# Payload_Electronics.net
KiCad netlist of a schematic drawn in EAGLE
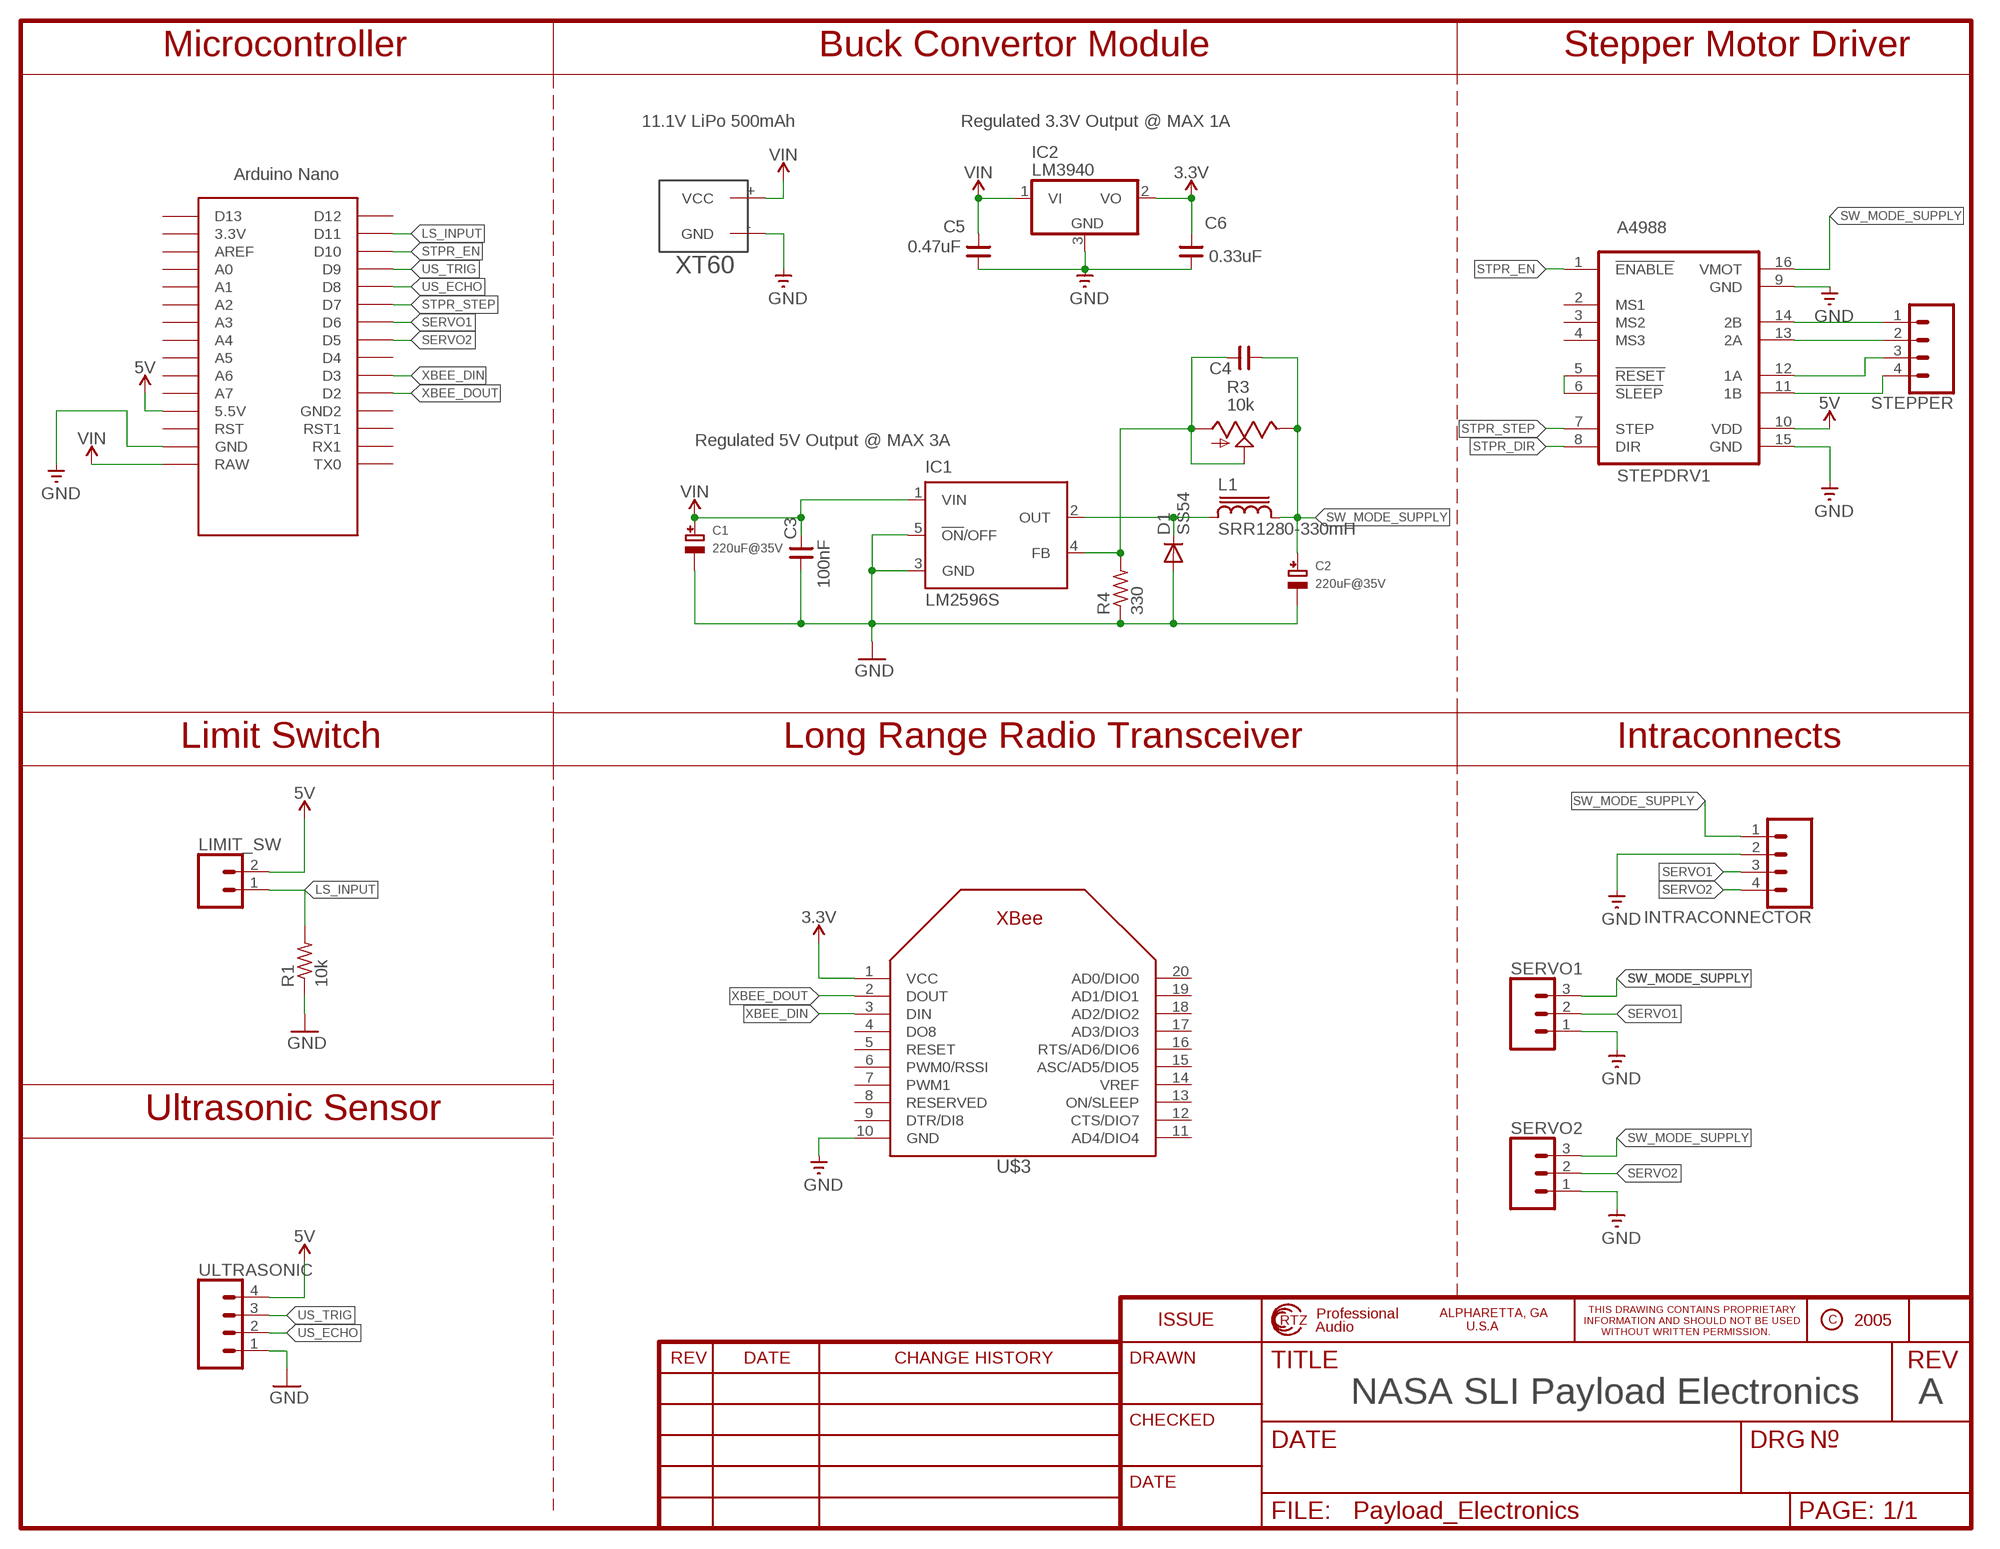
[diagram p0: schematic, sheet 1]

(export (version "E")
  (design (tool "Eeschema 10.0.6"))
  (components
    (comp (ref "C1")
      (value "220uF@35V")
      (footprint "eagle-import:PANASONIC_D")
      (libsource (lib "eagle-import") (part "CAP_ELECTROLYTICPANASONIC_D"))
    )
    (comp (ref "C2")
      (value "220uF@35V")
      (footprint "eagle-import:PANASONIC_D")
      (libsource (lib "eagle-import") (part "CAP_ELECTROLYTICPANASONIC_D"))
    )
    (comp (ref "C3")
      (value "100nF")
      (footprint "eagle-import:0603")
      (libsource (lib "eagle-import") (part "CNP-0603"))
    )
    (comp (ref "C4")
      (value "CNP-0603")
      (footprint "eagle-import:0603")
      (libsource (lib "eagle-import") (part "CNP-0603"))
    )
    (comp (ref "C5")
      (value "0.47uF")
      (footprint "eagle-import:0805")
      (libsource (lib "eagle-import") (part "CNP-0805"))
    )
    (comp (ref "C6")
      (value "0.33uF")
      (footprint "eagle-import:0805")
      (libsource (lib "eagle-import") (part "CNP-0805"))
    )
    (comp (ref "D1")
      (value "SS54")
      (footprint "eagle-import:DO214AB")
      (fields (field (name "MF") "Fairchild") (field (name "MPN") "S3G"))
      (libsource (lib "eagle-import") (part "S3G"))
    )
    (comp (ref "IC1")
      (value "LM2596S")
      (footprint "eagle-import:TO263-5")
      (fields (field (name "MF") "NATIONAL SEMICONDUCTOR") (field (name "MPN") "LM2596S-ADJ/NOPB"))
      (libsource (lib "eagle-import") (part "LM2596S"))
    )
    (comp (ref "IC2")
      (value "LM3940")
      (footprint "eagle-import:TO252")
      (libsource (lib "eagle-import") (part "78DT15"))
    )
    (comp (ref "INTRACONNECTOR")
      (value "CONN_04")
      (footprint "eagle-import:1X04")
      (libsource (lib "eagle-import") (part "CONN_04"))
    )
    (comp (ref "L1")
      (value "SRR1280-330mH")
      (footprint "eagle-import:SRR1280")
      (libsource (lib "eagle-import") (part "SRR1280"))
    )
    (comp (ref "LIMIT_SW")
      (value "CONN_02")
      (footprint "eagle-import:1X02")
      (libsource (lib "eagle-import") (part "CONN_02"))
    )
    (comp (ref "R1")
      (value "10k")
      (footprint "eagle-import:M0805")
      (libsource (lib "eagle-import") (part "R-US_M0805"))
    )
    (comp (ref "R3")
      (value "10k")
      (footprint "eagle-import:S64W")
      (libsource (lib "eagle-import") (part "TRIM_US-S64W"))
    )
    (comp (ref "R4")
      (value "330")
      (footprint "eagle-import:R0603")
      (libsource (lib "eagle-import") (part "R-US_R0603"))
    )
    (comp (ref "SERVO1")
      (value "CONN_03")
      (footprint "eagle-import:1X03")
      (libsource (lib "eagle-import") (part "CONN_03"))
    )
    (comp (ref "SERVO2")
      (value "CONN_03")
      (footprint "eagle-import:1X03")
      (libsource (lib "eagle-import") (part "CONN_03"))
    )
    (comp (ref "STEPDRV1")
      (value "A4988")
      (footprint "eagle-import:POLOLULU2128")
      (libsource (lib "eagle-import") (part "POLOLULU2128"))
    )
    (comp (ref "STEPPER")
      (value "CONN_04")
      (footprint "eagle-import:1X04")
      (libsource (lib "eagle-import") (part "CONN_04"))
    )
    (comp (ref "U$1")
      (value "NANO")
      (footprint "eagle-import:NANO")
      (libsource (lib "eagle-import") (part "NANO"))
    )
    (comp (ref "U$2")
      (value "XT60")
      (footprint "eagle-import:XT60")
      (libsource (lib "eagle-import") (part "XT60"))
    )
    (comp (ref "U$3")
      (value "XBEE")
      (footprint "eagle-import:XBEE")
      (libsource (lib "eagle-import") (part "XBEE"))
    )
    (comp (ref "ULTRASONIC")
      (value "CONN_04")
      (footprint "eagle-import:1X04")
      (libsource (lib "eagle-import") (part "CONN_04"))
    )
  )
  (nets
    (net (code "1") (name "3.3V") (class "Default")
      (node (ref "C6") (pin "2") (pinfunction "2_2") (pintype "passive"))
      (node (ref "IC2") (pin "2") (pinfunction "VO_2") (pintype "passive"))
      (node (ref "U$3") (pin "1") (pinfunction "VCC_1") (pintype "power_in"))
    )
    (net (code "2") (name "5V") (class "Default")
      (node (ref "LIMIT_SW") (pin "2") (pinfunction "2_2") (pintype "passive"))
      (node (ref "STEPDRV1") (pin "10") (pinfunction "VDD_10") (pintype "power_in"))
      (node (ref "U$1") (pin "5V") (pinfunction "5.5V_5V") (pintype "bidirectional"))
      (node (ref "ULTRASONIC") (pin "4") (pinfunction "4_4") (pintype "passive"))
    )
    (net (code "3") (name "GND") (class "Default")
      (node (ref "C1") (pin "-") (pinfunction "-_-") (pintype "passive"))
      (node (ref "C2") (pin "-") (pinfunction "-_-") (pintype "passive"))
      (node (ref "C3") (pin "1") (pinfunction "1_1") (pintype "passive"))
      (node (ref "C5") (pin "1") (pinfunction "1_1") (pintype "passive"))
      (node (ref "C6") (pin "1") (pinfunction "1_1") (pintype "passive"))
      (node (ref "D1") (pin "A") (pinfunction "A_A") (pintype "passive"))
      (node (ref "IC1") (pin "3") (pinfunction "GND_3") (pintype "power_in"))
      (node (ref "IC1") (pin "5") (pinfunction "~{ON}/OFF_5") (pintype "input"))
      (node (ref "IC2") (pin "3") (pinfunction "GND_3") (pintype "passive"))
      (node (ref "INTRACONNECTOR") (pin "2") (pinfunction "2_2") (pintype "passive"))
      (node (ref "R1") (pin "1") (pinfunction "1_1") (pintype "passive"))
      (node (ref "R4") (pin "1") (pinfunction "1_1") (pintype "passive"))
      (node (ref "SERVO1") (pin "1") (pinfunction "1_1") (pintype "passive"))
      (node (ref "SERVO2") (pin "1") (pinfunction "1_1") (pintype "passive"))
      (node (ref "STEPDRV1") (pin "15") (pinfunction "GND_15") (pintype "power_in"))
      (node (ref "STEPDRV1") (pin "9") (pinfunction "GND_9") (pintype "power_in"))
      (node (ref "U$1") (pin "GND") (pinfunction "GND_GND") (pintype "bidirectional"))
      (node (ref "U$2") (pin "-") (pinfunction "GND_-") (pintype "bidirectional"))
      (node (ref "U$3") (pin "10") (pinfunction "GND_10") (pintype "power_in"))
      (node (ref "ULTRASONIC") (pin "1") (pinfunction "1_1") (pintype "passive"))
    )
    (net (code "4") (name "LS_INPUT") (class "Default")
      (node (ref "LIMIT_SW") (pin "1") (pinfunction "1_1") (pintype "passive"))
      (node (ref "R1") (pin "2") (pinfunction "2_2") (pintype "passive"))
      (node (ref "U$1") (pin "D11") (pinfunction "D11_D11") (pintype "bidirectional"))
    )
    (net (code "5") (name "Net-(IC1-FB)") (class "Default")
      (node (ref "C4") (pin "2") (pinfunction "2_2") (pintype "passive"))
      (node (ref "IC1") (pin "4") (pinfunction "FB_4") (pintype "input"))
      (node (ref "R3") (pin "A") (pinfunction "A_A") (pintype "passive"))
      (node (ref "R3") (pin "S") (pinfunction "S_S") (pintype "passive"))
      (node (ref "R4") (pin "2") (pinfunction "2_2") (pintype "passive"))
    )
    (net (code "6") (name "Net-(IC1-OUT)") (class "Default")
      (node (ref "D1") (pin "C") (pinfunction "C_C") (pintype "passive"))
      (node (ref "IC1") (pin "2") (pinfunction "OUT_2") (pintype "output"))
      (node (ref "L1") (pin "1") (pinfunction "1_1") (pintype "passive"))
    )
    (net (code "7") (name "Net-(STEPDRV1-1A)") (class "Default")
      (node (ref "STEPDRV1") (pin "12") (pinfunction "1A_12") (pintype "output"))
      (node (ref "STEPPER") (pin "3") (pinfunction "3_3") (pintype "passive"))
    )
    (net (code "8") (name "Net-(STEPDRV1-1B)") (class "Default")
      (node (ref "STEPDRV1") (pin "11") (pinfunction "1B_11") (pintype "output"))
      (node (ref "STEPPER") (pin "4") (pinfunction "4_4") (pintype "passive"))
    )
    (net (code "9") (name "Net-(STEPDRV1-2A)") (class "Default")
      (node (ref "STEPDRV1") (pin "13") (pinfunction "2A_13") (pintype "output"))
      (node (ref "STEPPER") (pin "2") (pinfunction "2_2") (pintype "passive"))
    )
    (net (code "10") (name "Net-(STEPDRV1-2B)") (class "Default")
      (node (ref "STEPDRV1") (pin "14") (pinfunction "2B_14") (pintype "output"))
      (node (ref "STEPPER") (pin "1") (pinfunction "1_1") (pintype "passive"))
    )
    (net (code "11") (name "Net-(STEPDRV1-~{RESET})") (class "Default")
      (node (ref "STEPDRV1") (pin "5") (pinfunction "~{RESET}_5") (pintype "input"))
      (node (ref "STEPDRV1") (pin "6") (pinfunction "~{SLEEP}_6") (pintype "input"))
    )
    (net (code "12") (name "SERVO1") (class "Default")
      (node (ref "INTRACONNECTOR") (pin "3") (pinfunction "3_3") (pintype "passive"))
      (node (ref "SERVO1") (pin "2") (pinfunction "2_2") (pintype "passive"))
      (node (ref "U$1") (pin "D6") (pinfunction "D6_D6") (pintype "bidirectional"))
    )
    (net (code "13") (name "SERVO2") (class "Default")
      (node (ref "INTRACONNECTOR") (pin "4") (pinfunction "4_4") (pintype "passive"))
      (node (ref "SERVO2") (pin "2") (pinfunction "2_2") (pintype "passive"))
      (node (ref "U$1") (pin "D5") (pinfunction "D5_D5") (pintype "bidirectional"))
    )
    (net (code "14") (name "STPR_DIR") (class "Default")
      (node (ref "STEPDRV1") (pin "8") (pinfunction "DIR_8") (pintype "input"))
    )
    (net (code "15") (name "STPR_EN") (class "Default")
      (node (ref "STEPDRV1") (pin "1") (pinfunction "~{ENABLE}_1") (pintype "input"))
      (node (ref "U$1") (pin "D10") (pinfunction "D10_D10") (pintype "bidirectional"))
    )
    (net (code "16") (name "STPR_STEP") (class "Default")
      (node (ref "STEPDRV1") (pin "7") (pinfunction "STEP_7") (pintype "input"))
      (node (ref "U$1") (pin "D7") (pinfunction "D7_D7") (pintype "bidirectional"))
    )
    (net (code "17") (name "SW_MODE_SUPPLY") (class "Default")
      (node (ref "C2") (pin "+") (pinfunction "+_+") (pintype "passive"))
      (node (ref "C4") (pin "1") (pinfunction "1_1") (pintype "passive"))
      (node (ref "INTRACONNECTOR") (pin "1") (pinfunction "1_1") (pintype "passive"))
      (node (ref "L1") (pin "2") (pinfunction "2_2") (pintype "passive"))
      (node (ref "R3") (pin "E") (pinfunction "E_E") (pintype "passive"))
      (node (ref "SERVO1") (pin "3") (pinfunction "3_3") (pintype "passive"))
      (node (ref "SERVO2") (pin "3") (pinfunction "3_3") (pintype "passive"))
      (node (ref "STEPDRV1") (pin "16") (pinfunction "VMOT_16") (pintype "power_in"))
    )
    (net (code "18") (name "US_ECHO") (class "Default")
      (node (ref "U$1") (pin "D8") (pinfunction "D8_D8") (pintype "bidirectional"))
      (node (ref "ULTRASONIC") (pin "2") (pinfunction "2_2") (pintype "passive"))
    )
    (net (code "19") (name "US_TRIG") (class "Default")
      (node (ref "U$1") (pin "D9") (pinfunction "D9_D9") (pintype "bidirectional"))
      (node (ref "ULTRASONIC") (pin "3") (pinfunction "3_3") (pintype "passive"))
    )
    (net (code "20") (name "VIN") (class "Default")
      (node (ref "C1") (pin "+") (pinfunction "+_+") (pintype "passive"))
      (node (ref "C3") (pin "2") (pinfunction "2_2") (pintype "passive"))
      (node (ref "C5") (pin "2") (pinfunction "2_2") (pintype "passive"))
      (node (ref "IC1") (pin "1") (pinfunction "VIN_1") (pintype "input"))
      (node (ref "IC2") (pin "1") (pinfunction "VI_1") (pintype "input"))
      (node (ref "U$1") (pin "RAW") (pinfunction "RAW_RAW") (pintype "bidirectional"))
      (node (ref "U$2") (pin "+") (pinfunction "VCC_+") (pintype "bidirectional"))
    )
    (net (code "21") (name "XBEE_DIN") (class "Default")
      (node (ref "U$1") (pin "D3") (pinfunction "D3_D3") (pintype "bidirectional"))
      (node (ref "U$3") (pin "3") (pinfunction "DIN_3") (pintype "input"))
    )
    (net (code "22") (name "XBEE_DOUT") (class "Default")
      (node (ref "U$1") (pin "D2") (pinfunction "D2_D2") (pintype "bidirectional"))
      (node (ref "U$3") (pin "2") (pinfunction "DOUT_2") (pintype "output"))
    )
    (net (code "23") (name "unconnected-(STEPDRV1-MS1-Pad2)") (class "Default")
      (node (ref "STEPDRV1") (pin "2") (pinfunction "MS1_2") (pintype "input"))
    )
    (net (code "24") (name "unconnected-(STEPDRV1-MS2-Pad3)") (class "Default")
      (node (ref "STEPDRV1") (pin "3") (pinfunction "MS2_3") (pintype "input"))
    )
    (net (code "25") (name "unconnected-(STEPDRV1-MS3-Pad4)") (class "Default")
      (node (ref "STEPDRV1") (pin "4") (pinfunction "MS3_4") (pintype "input"))
    )
    (net (code "26") (name "unconnected-(U$1-GND2-PadGND1)") (class "Default")
      (node (ref "U$1") (pin "GND1") (pinfunction "GND2_GND1") (pintype "bidirectional"))
    )
    (net (code "27") (name "unconnected-(U$1-Pad3.3V)") (class "Default")
      (node (ref "U$1") (pin "3.3V") (pinfunction "3.3V_3.3V") (pintype "bidirectional"))
    )
    (net (code "28") (name "unconnected-(U$1-PadA0)") (class "Default")
      (node (ref "U$1") (pin "A0") (pinfunction "A0_A0") (pintype "bidirectional"))
    )
    (net (code "29") (name "unconnected-(U$1-PadA1)") (class "Default")
      (node (ref "U$1") (pin "A1") (pinfunction "A1_A1") (pintype "bidirectional"))
    )
    (net (code "30") (name "unconnected-(U$1-PadA2)") (class "Default")
      (node (ref "U$1") (pin "A2") (pinfunction "A2_A2") (pintype "bidirectional"))
    )
    (net (code "31") (name "unconnected-(U$1-PadA3)") (class "Default")
      (node (ref "U$1") (pin "A3") (pinfunction "A3_A3") (pintype "bidirectional"))
    )
    (net (code "32") (name "unconnected-(U$1-PadA4)") (class "Default")
      (node (ref "U$1") (pin "A4") (pinfunction "A4_A4") (pintype "bidirectional"))
    )
    (net (code "33") (name "unconnected-(U$1-PadA5)") (class "Default")
      (node (ref "U$1") (pin "A5") (pinfunction "A5_A5") (pintype "bidirectional"))
    )
    (net (code "34") (name "unconnected-(U$1-PadA6)") (class "Default")
      (node (ref "U$1") (pin "A6") (pinfunction "A6_A6") (pintype "bidirectional"))
    )
    (net (code "35") (name "unconnected-(U$1-PadA7)") (class "Default")
      (node (ref "U$1") (pin "A7") (pinfunction "A7_A7") (pintype "bidirectional"))
    )
    (net (code "36") (name "unconnected-(U$1-PadAREF)") (class "Default")
      (node (ref "U$1") (pin "AREF") (pinfunction "AREF_AREF") (pintype "bidirectional"))
    )
    (net (code "37") (name "unconnected-(U$1-PadD4)") (class "Default")
      (node (ref "U$1") (pin "D4") (pinfunction "D4_D4") (pintype "bidirectional"))
    )
    (net (code "38") (name "unconnected-(U$1-PadD12)") (class "Default")
      (node (ref "U$1") (pin "D12") (pinfunction "D12_D12") (pintype "bidirectional"))
    )
    (net (code "39") (name "unconnected-(U$1-PadD13)") (class "Default")
      (node (ref "U$1") (pin "D13") (pinfunction "D13_D13") (pintype "bidirectional"))
    )
    (net (code "40") (name "unconnected-(U$1-PadICSP1)") (class "Default")
      (node (ref "U$1") (pin "ICSP1") (pinfunction "ICSP1_ICSP1") (pintype "bidirectional"))
    )
    (net (code "41") (name "unconnected-(U$1-PadICSP2)") (class "Default")
      (node (ref "U$1") (pin "ICSP2") (pinfunction "ICSP2_ICSP2") (pintype "bidirectional"))
    )
    (net (code "42") (name "unconnected-(U$1-PadICSP3)") (class "Default")
      (node (ref "U$1") (pin "ICSP3") (pinfunction "ICSP3_ICSP3") (pintype "bidirectional"))
    )
    (net (code "43") (name "unconnected-(U$1-PadICSP4)") (class "Default")
      (node (ref "U$1") (pin "ICSP4") (pinfunction "ICSP4_ICSP4") (pintype "bidirectional"))
    )
    (net (code "44") (name "unconnected-(U$1-PadICSP5)") (class "Default")
      (node (ref "U$1") (pin "ICSP5") (pinfunction "ICSP5_ICSP5") (pintype "bidirectional"))
    )
    (net (code "45") (name "unconnected-(U$1-PadICSP6)") (class "Default")
      (node (ref "U$1") (pin "ICSP6") (pinfunction "ICSP6_ICSP6") (pintype "bidirectional"))
    )
    (net (code "46") (name "unconnected-(U$1-PadRST)") (class "Default")
      (node (ref "U$1") (pin "RST") (pinfunction "RST_RST") (pintype "bidirectional"))
    )
    (net (code "47") (name "unconnected-(U$1-PadRST1)") (class "Default")
      (node (ref "U$1") (pin "RST1") (pinfunction "RST1_RST1") (pintype "bidirectional"))
    )
    (net (code "48") (name "unconnected-(U$1-PadRX1)") (class "Default")
      (node (ref "U$1") (pin "RX1") (pinfunction "RX1_RX1") (pintype "bidirectional"))
    )
    (net (code "49") (name "unconnected-(U$1-PadTX0)") (class "Default")
      (node (ref "U$1") (pin "TX0") (pinfunction "TX0_TX0") (pintype "bidirectional"))
    )
    (net (code "50") (name "unconnected-(U$3-AD0{slash}DIO0-Pad20)") (class "Default")
      (node (ref "U$3") (pin "20") (pinfunction "AD0/DIO0_20") (pintype "bidirectional"))
    )
    (net (code "51") (name "unconnected-(U$3-AD1{slash}DIO1-Pad19)") (class "Default")
      (node (ref "U$3") (pin "19") (pinfunction "AD1/DIO1_19") (pintype "bidirectional"))
    )
    (net (code "52") (name "unconnected-(U$3-AD2{slash}DIO2-Pad18)") (class "Default")
      (node (ref "U$3") (pin "18") (pinfunction "AD2/DIO2_18") (pintype "bidirectional"))
    )
    (net (code "53") (name "unconnected-(U$3-AD3{slash}DIO3-Pad17)") (class "Default")
      (node (ref "U$3") (pin "17") (pinfunction "AD3/DIO3_17") (pintype "bidirectional"))
    )
    (net (code "54") (name "unconnected-(U$3-AD4{slash}DIO4-Pad11)") (class "Default")
      (node (ref "U$3") (pin "11") (pinfunction "AD4/DIO4_11") (pintype "bidirectional"))
    )
    (net (code "55") (name "unconnected-(U$3-ASC{slash}AD5{slash}DIO5-Pad15)") (class "Default")
      (node (ref "U$3") (pin "15") (pinfunction "ASC/AD5/DIO5_15") (pintype "bidirectional"))
    )
    (net (code "56") (name "unconnected-(U$3-CTS{slash}DIO7-Pad12)") (class "Default")
      (node (ref "U$3") (pin "12") (pinfunction "CTS/DIO7_12") (pintype "bidirectional"))
    )
    (net (code "57") (name "unconnected-(U$3-DO8-Pad4)") (class "Default")
      (node (ref "U$3") (pin "4") (pinfunction "DO8_4") (pintype "output"))
    )
    (net (code "58") (name "unconnected-(U$3-DTR{slash}DI8-Pad9)") (class "Default")
      (node (ref "U$3") (pin "9") (pinfunction "DTR/DI8_9") (pintype "input"))
    )
    (net (code "59") (name "unconnected-(U$3-ON{slash}SLEEP-Pad13)") (class "Default")
      (node (ref "U$3") (pin "13") (pinfunction "ON/SLEEP_13") (pintype "output"))
    )
    (net (code "60") (name "unconnected-(U$3-PWM0{slash}RSSI-Pad6)") (class "Default")
      (node (ref "U$3") (pin "6") (pinfunction "PWM0/RSSI_6") (pintype "output"))
    )
    (net (code "61") (name "unconnected-(U$3-PWM1-Pad7)") (class "Default")
      (node (ref "U$3") (pin "7") (pinfunction "PWM1_7") (pintype "output"))
    )
    (net (code "62") (name "unconnected-(U$3-RESERVED-Pad8)") (class "Default")
      (node (ref "U$3") (pin "8") (pinfunction "RESERVED_8") (pintype "no_connect"))
    )
    (net (code "63") (name "unconnected-(U$3-RESET-Pad5)") (class "Default")
      (node (ref "U$3") (pin "5") (pinfunction "RESET_5") (pintype "input"))
    )
    (net (code "64") (name "unconnected-(U$3-RTS{slash}AD6{slash}DIO6-Pad16)") (class "Default")
      (node (ref "U$3") (pin "16") (pinfunction "RTS/AD6/DIO6_16") (pintype "bidirectional"))
    )
    (net (code "65") (name "unconnected-(U$3-VREF-Pad14)") (class "Default")
      (node (ref "U$3") (pin "14") (pinfunction "VREF_14") (pintype "input"))
    )
  )
)
